# ESP_LoRa_1_0.net
KiCad netlist of a schematic drawn in EAGLE
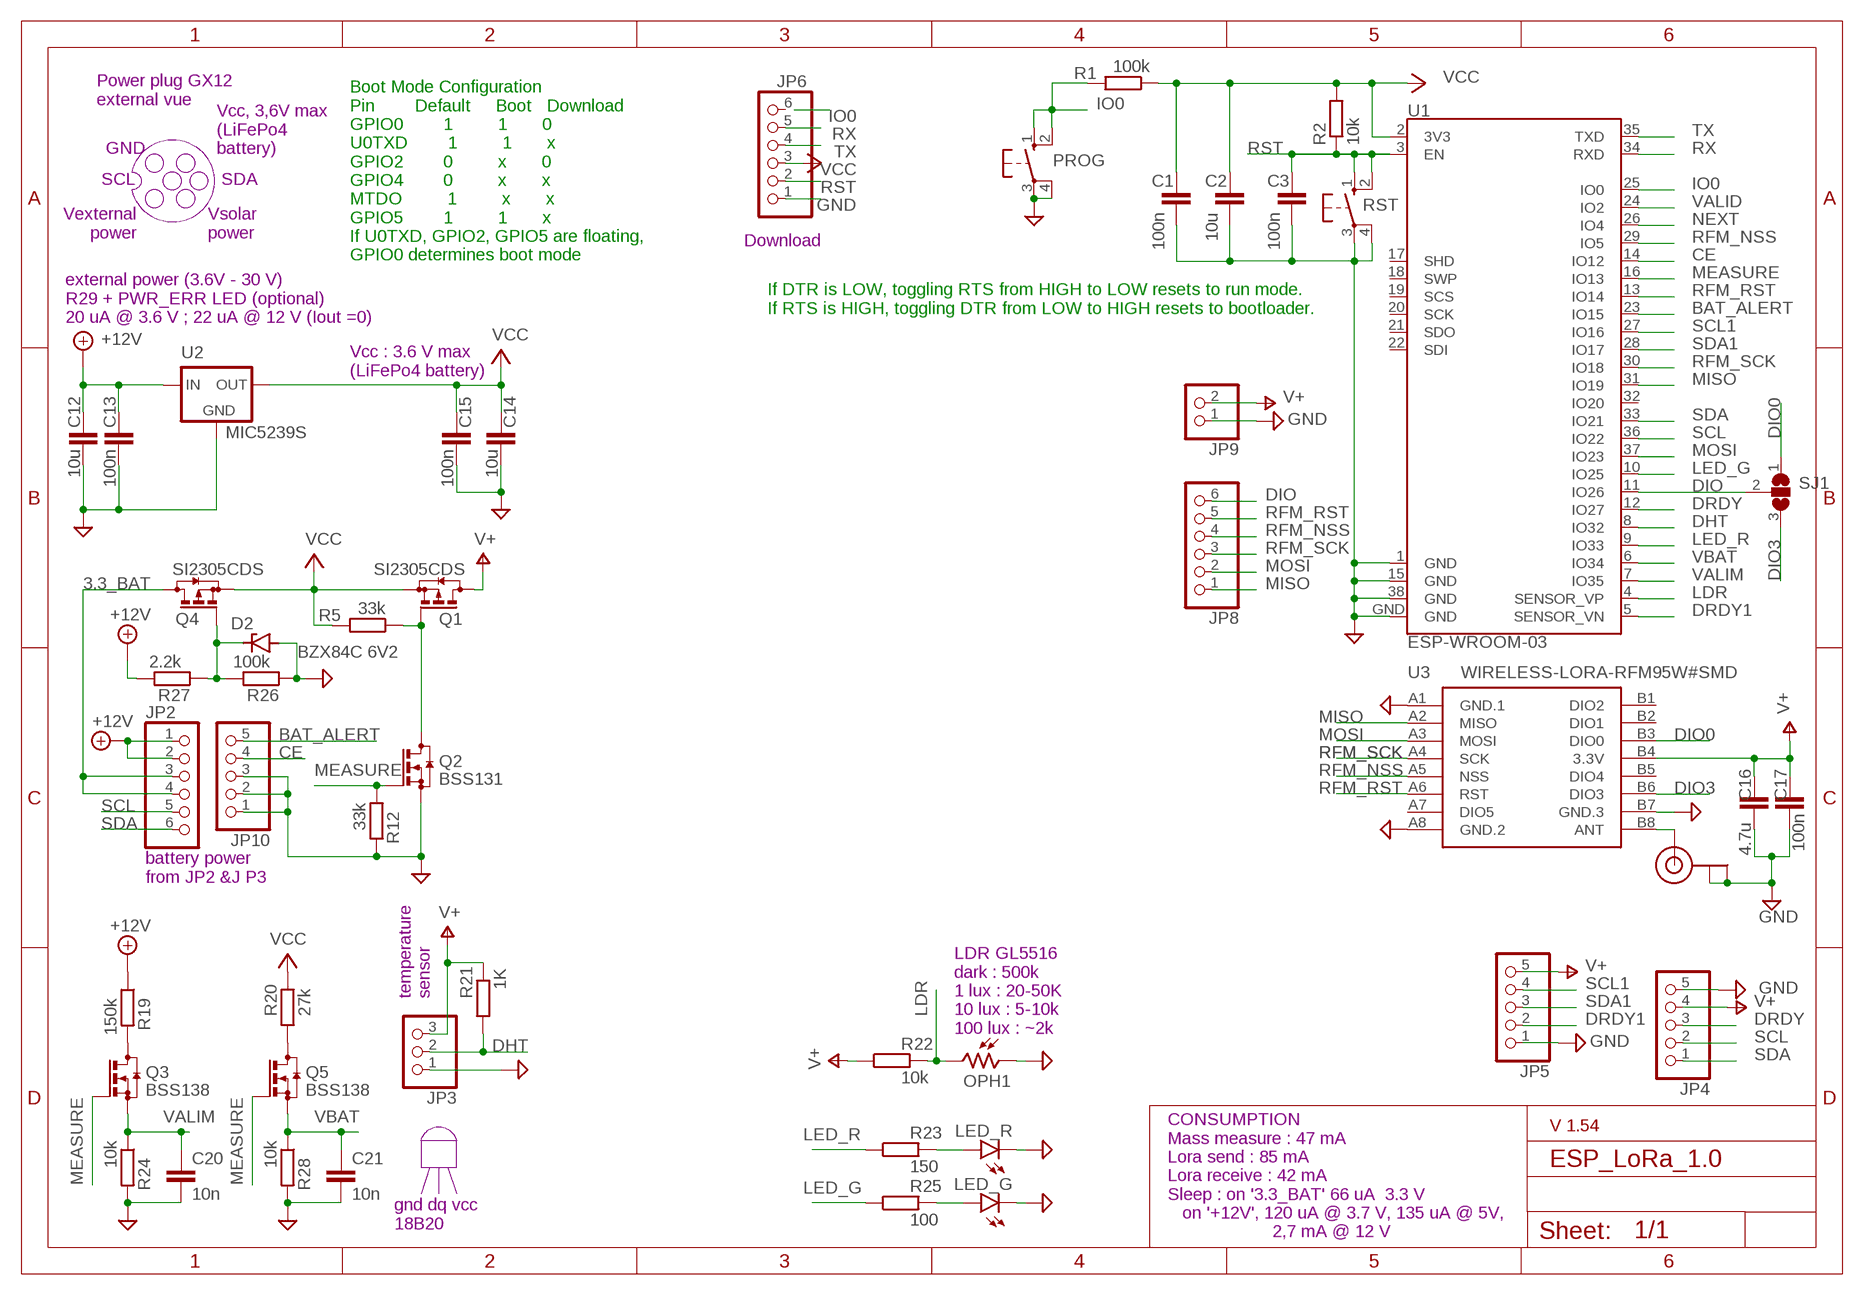
[diagram p0: schematic, sheet 1]

(export (version "E")
  (design (tool "Eeschema 10.0.6"))
  (components
    (comp (ref "C1")
      (value "100n")
      (footprint "eagle-import:C1206")
      (libsource (lib "eagle-import") (part "CC1206"))
    )
    (comp (ref "C2")
      (value "10u")
      (footprint "eagle-import:C1210")
      (libsource (lib "eagle-import") (part "CC1210"))
    )
    (comp (ref "C3")
      (value "100n")
      (footprint "eagle-import:C1206")
      (libsource (lib "eagle-import") (part "CC1206"))
    )
    (comp (ref "C12")
      (value "10u")
      (footprint "eagle-import:C1210")
      (libsource (lib "eagle-import") (part "CC1210"))
    )
    (comp (ref "C13")
      (value "100n")
      (footprint "eagle-import:C1206")
      (libsource (lib "eagle-import") (part "CC1206"))
    )
    (comp (ref "C14")
      (value "10u")
      (footprint "eagle-import:C1210")
      (libsource (lib "eagle-import") (part "CC1210"))
    )
    (comp (ref "C15")
      (value "100n")
      (footprint "eagle-import:C1206")
      (libsource (lib "eagle-import") (part "CC1206"))
    )
    (comp (ref "C16")
      (value "4.7u")
      (footprint "eagle-import:C1210")
      (libsource (lib "eagle-import") (part "CC1210"))
    )
    (comp (ref "C17")
      (value "100n")
      (footprint "eagle-import:C1206")
      (libsource (lib "eagle-import") (part "CC1206"))
    )
    (comp (ref "C20")
      (value "10n")
      (footprint "eagle-import:C1206")
      (libsource (lib "eagle-import") (part "CC1206"))
    )
    (comp (ref "C21")
      (value "10n")
      (footprint "eagle-import:C1206")
      (libsource (lib "eagle-import") (part "CC1206"))
    )
    (comp (ref "D2")
      (value "BZX84C 6V2")
      (footprint "eagle-import:TO236")
      (libsource (lib "eagle-import") (part "BZX84CSMD"))
    )
    (comp (ref "J1")
      (value "U.FL")
      (footprint "eagle-import:U.FL")
      (libsource (lib "eagle-import") (part "U.FL"))
    )
    (comp (ref "JP2")
      (value "PINHD-1X6")
      (footprint "eagle-import:1X06")
      (libsource (lib "eagle-import") (part "PINHD-1X6"))
    )
    (comp (ref "JP3")
      (value "PINHD-1X3")
      (footprint "eagle-import:1X03")
      (libsource (lib "eagle-import") (part "PINHD-1X3"))
    )
    (comp (ref "JP4")
      (value "PINHD-1X5")
      (footprint "eagle-import:1X05")
      (libsource (lib "eagle-import") (part "PINHD-1X5"))
    )
    (comp (ref "JP5")
      (value "PINHD-1X5")
      (footprint "eagle-import:1X05")
      (libsource (lib "eagle-import") (part "PINHD-1X5"))
    )
    (comp (ref "JP6")
      (value "PINHD-1X6")
      (footprint "eagle-import:1X06")
      (libsource (lib "eagle-import") (part "PINHD-1X6"))
    )
    (comp (ref "JP8")
      (value "PINHD-1X6")
      (footprint "eagle-import:1X06")
      (libsource (lib "eagle-import") (part "PINHD-1X6"))
    )
    (comp (ref "JP9")
      (value "PINHD-1X2")
      (footprint "eagle-import:1X02")
      (libsource (lib "eagle-import") (part "PINHD-1X2"))
    )
    (comp (ref "JP10")
      (value "PINHD-1X5")
      (footprint "eagle-import:1X05")
      (libsource (lib "eagle-import") (part "PINHD-1X5"))
    )
    (comp (ref "LED_G")
      (value "LEDSMT1206")
      (footprint "eagle-import:1206")
      (libsource (lib "eagle-import") (part "LEDSMT1206"))
    )
    (comp (ref "LED_R")
      (value "LEDSMT1206")
      (footprint "eagle-import:1206")
      (libsource (lib "eagle-import") (part "LEDSMT1206"))
    )
    (comp (ref "OPH1")
      (value "VT93N2")
      (footprint "eagle-import:VT900")
      (libsource (lib "eagle-import") (part "VT93N2"))
    )
    (comp (ref "PROG")
      (value "10-XX")
      (footprint "eagle-import:B3F-10XX")
      (fields (field (name "MPN") "B3F-1000"))
      (libsource (lib "eagle-import") (part "10-XX"))
    )
    (comp (ref "Q1")
      (value "SI2305CDS")
      (footprint "eagle-import:SOT23")
      (libsource (lib "eagle-import") (part "SI2305CDS"))
    )
    (comp (ref "Q2")
      (value "BSS131")
      (footprint "eagle-import:SOT23")
      (libsource (lib "eagle-import") (part "BSS131"))
    )
    (comp (ref "Q3")
      (value "BSS138")
      (footprint "eagle-import:SOT23")
      (libsource (lib "eagle-import") (part "BSS138"))
    )
    (comp (ref "Q4")
      (value "SI2305CDS")
      (footprint "eagle-import:SOT23")
      (libsource (lib "eagle-import") (part "SI2305CDS"))
    )
    (comp (ref "Q5")
      (value "BSS138")
      (footprint "eagle-import:SOT23")
      (libsource (lib "eagle-import") (part "BSS138"))
    )
    (comp (ref "R1")
      (value "100k")
      (footprint "eagle-import:R1206")
      (libsource (lib "eagle-import") (part "RR1206"))
    )
    (comp (ref "R2")
      (value "10k")
      (footprint "eagle-import:R1206")
      (libsource (lib "eagle-import") (part "RR1206"))
    )
    (comp (ref "R5")
      (value "33k")
      (footprint "eagle-import:R1206")
      (libsource (lib "eagle-import") (part "RR1206"))
    )
    (comp (ref "R12")
      (value "33k")
      (footprint "eagle-import:R1206")
      (libsource (lib "eagle-import") (part "RR1206"))
    )
    (comp (ref "R19")
      (value "150k")
      (footprint "eagle-import:R1206")
      (libsource (lib "eagle-import") (part "RR1206"))
    )
    (comp (ref "R20")
      (value "27k")
      (footprint "eagle-import:R1206")
      (libsource (lib "eagle-import") (part "RR1206"))
    )
    (comp (ref "R21")
      (value "1K")
      (footprint "eagle-import:R1206")
      (libsource (lib "eagle-import") (part "RR1206"))
    )
    (comp (ref "R22")
      (value "10k")
      (footprint "eagle-import:R1206")
      (libsource (lib "eagle-import") (part "RR1206"))
    )
    (comp (ref "R23")
      (value "150")
      (footprint "eagle-import:R1206")
      (libsource (lib "eagle-import") (part "RR1206"))
    )
    (comp (ref "R24")
      (value "10k")
      (footprint "eagle-import:R1206")
      (libsource (lib "eagle-import") (part "RR1206"))
    )
    (comp (ref "R25")
      (value "100")
      (footprint "eagle-import:R1206")
      (libsource (lib "eagle-import") (part "RR1206"))
    )
    (comp (ref "R26")
      (value "100k")
      (footprint "eagle-import:R1206")
      (libsource (lib "eagle-import") (part "RR1206"))
    )
    (comp (ref "R27")
      (value "2.2k")
      (footprint "eagle-import:R1206")
      (libsource (lib "eagle-import") (part "RR1206"))
    )
    (comp (ref "R28")
      (value "10k")
      (footprint "eagle-import:R1206")
      (libsource (lib "eagle-import") (part "RR1206"))
    )
    (comp (ref "RST")
      (value "10-XX")
      (footprint "eagle-import:B3F-10XX")
      (fields (field (name "MPN") "B3F-1000"))
      (libsource (lib "eagle-import") (part "10-XX"))
    )
    (comp (ref "SJ1")
      (value "SJ2W")
      (footprint "eagle-import:SJ_2")
      (libsource (lib "eagle-import") (part "SJ2W"))
    )
    (comp (ref "U1")
      (value "ESP-WROOM-03")
      (footprint "eagle-import:ESP-WROOM-03")
      (libsource (lib "eagle-import") (part "ESP-WROOM-03"))
    )
    (comp (ref "U2")
      (value "MIC5239S")
      (footprint "eagle-import:SOT223")
      (libsource (lib "eagle-import") (part "MIC5239S"))
    )
    (comp (ref "U3")
      (value "WIRELESS-LORA-RFM95W#SMD")
      (footprint "eagle-import:WIRELESS-LORA-RFM95W#SMD")
      (libsource (lib "eagle-import") (part "WIRELESS-LORA-RFM95W#SMD"))
    )
  )
  (nets
    (net (code "1") (name "+12V") (class "Default")
      (node (ref "C12") (pin "1") (pinfunction "1_1") (pintype "passive"))
      (node (ref "C13") (pin "1") (pinfunction "1_1") (pintype "passive"))
      (node (ref "JP2") (pin "1") (pinfunction "1_1") (pintype "passive"))
      (node (ref "JP2") (pin "2") (pinfunction "2_2") (pintype "passive"))
      (node (ref "R19") (pin "1") (pinfunction "1_1") (pintype "passive"))
      (node (ref "R27") (pin "2") (pinfunction "2_2") (pintype "passive"))
      (node (ref "U2") (pin "1") (pinfunction "IN_1") (pintype "input"))
    )
    (net (code "2") (name "/3.3_BAT") (class "Default")
      (node (ref "JP2") (pin "3") (pinfunction "3_3") (pintype "passive"))
      (node (ref "JP2") (pin "4") (pinfunction "4_4") (pintype "passive"))
      (node (ref "Q4") (pin "3") (pinfunction "D_3") (pintype "passive"))
    )
    (net (code "3") (name "/BAT_ALERT") (class "Default")
      (node (ref "JP10") (pin "5") (pinfunction "5_5") (pintype "passive"))
      (node (ref "U1") (pin "23") (pinfunction "IO15_23") (pintype "bidirectional"))
    )
    (net (code "4") (name "/CE") (class "Default")
      (node (ref "JP10") (pin "4") (pinfunction "4_4") (pintype "passive"))
      (node (ref "U1") (pin "14") (pinfunction "IO12_14") (pintype "bidirectional"))
    )
    (net (code "5") (name "/DHT") (class "Default")
      (node (ref "JP3") (pin "2") (pinfunction "2_2") (pintype "passive"))
      (node (ref "R21") (pin "1") (pinfunction "1_1") (pintype "passive"))
      (node (ref "U1") (pin "8") (pinfunction "IO32_8") (pintype "bidirectional"))
    )
    (net (code "6") (name "/DIO") (class "Default")
      (node (ref "JP8") (pin "6") (pinfunction "6_6") (pintype "passive"))
      (node (ref "SJ1") (pin "2") (pinfunction "2_2") (pintype "passive"))
      (node (ref "U1") (pin "11") (pinfunction "IO26_11") (pintype "bidirectional"))
    )
    (net (code "7") (name "/DIO0") (class "Default")
      (node (ref "SJ1") (pin "1") (pinfunction "1_1") (pintype "passive"))
      (node (ref "U3") (pin "B3") (pinfunction "DIO0_B3") (pintype "bidirectional"))
    )
    (net (code "8") (name "/DIO3") (class "Default")
      (node (ref "SJ1") (pin "3") (pinfunction "3_3") (pintype "passive"))
      (node (ref "U3") (pin "B6") (pinfunction "DIO3_B6") (pintype "bidirectional"))
    )
    (net (code "9") (name "/DRDY") (class "Default")
      (node (ref "JP4") (pin "3") (pinfunction "3_3") (pintype "passive"))
      (node (ref "U1") (pin "12") (pinfunction "IO27_12") (pintype "bidirectional"))
    )
    (net (code "10") (name "/DRDY1") (class "Default")
      (node (ref "JP5") (pin "2") (pinfunction "2_2") (pintype "passive"))
      (node (ref "U1") (pin "5") (pinfunction "SENSOR_VN_5") (pintype "bidirectional"))
    )
    (net (code "11") (name "/IO0") (class "Default")
      (node (ref "PROG") (pin "1") (pinfunction "S_1") (pintype "passive"))
      (node (ref "PROG") (pin "2") (pinfunction "S1_2") (pintype "passive"))
      (node (ref "R1") (pin "2") (pinfunction "2_2") (pintype "passive"))
      (node (ref "U1") (pin "25") (pinfunction "IO0_25") (pintype "bidirectional"))
    )
    (net (code "12") (name "/LDR") (class "Default")
      (node (ref "OPH1") (pin "2") (pinfunction "2_2") (pintype "passive"))
      (node (ref "R22") (pin "2") (pinfunction "2_2") (pintype "passive"))
      (node (ref "U1") (pin "4") (pinfunction "SENSOR_VP_4") (pintype "bidirectional"))
    )
    (net (code "13") (name "/LED_G") (class "Default")
      (node (ref "R25") (pin "1") (pinfunction "1_1") (pintype "passive"))
      (node (ref "U1") (pin "10") (pinfunction "IO25_10") (pintype "bidirectional"))
    )
    (net (code "14") (name "/LED_R") (class "Default")
      (node (ref "R23") (pin "1") (pinfunction "1_1") (pintype "passive"))
      (node (ref "U1") (pin "9") (pinfunction "IO33_9") (pintype "bidirectional"))
    )
    (net (code "15") (name "/MEASURE") (class "Default")
      (node (ref "Q2") (pin "1") (pinfunction "G_1") (pintype "passive"))
      (node (ref "Q3") (pin "1") (pinfunction "G_1") (pintype "passive"))
      (node (ref "Q5") (pin "1") (pinfunction "G_1") (pintype "passive"))
      (node (ref "R12") (pin "1") (pinfunction "1_1") (pintype "passive"))
      (node (ref "U1") (pin "16") (pinfunction "IO13_16") (pintype "bidirectional"))
    )
    (net (code "16") (name "/MISO") (class "Default")
      (node (ref "JP8") (pin "1") (pinfunction "1_1") (pintype "passive"))
      (node (ref "U1") (pin "31") (pinfunction "IO19_31") (pintype "bidirectional"))
      (node (ref "U3") (pin "A2") (pinfunction "MISO_A2") (pintype "bidirectional"))
    )
    (net (code "17") (name "/MOSI") (class "Default")
      (node (ref "JP8") (pin "2") (pinfunction "2_2") (pintype "passive"))
      (node (ref "U1") (pin "37") (pinfunction "IO23_37") (pintype "bidirectional"))
      (node (ref "U3") (pin "A3") (pinfunction "MOSI_A3") (pintype "bidirectional"))
    )
    (net (code "18") (name "/NEXT") (class "Default")
      (node (ref "U1") (pin "26") (pinfunction "IO4_26") (pintype "bidirectional"))
    )
    (net (code "19") (name "/RFM_NSS") (class "Default")
      (node (ref "JP8") (pin "4") (pinfunction "4_4") (pintype "passive"))
      (node (ref "U1") (pin "29") (pinfunction "IO5_29") (pintype "bidirectional"))
      (node (ref "U3") (pin "A5") (pinfunction "NSS_A5") (pintype "bidirectional"))
    )
    (net (code "20") (name "/RFM_RST") (class "Default")
      (node (ref "JP8") (pin "5") (pinfunction "5_5") (pintype "passive"))
      (node (ref "U1") (pin "13") (pinfunction "IO14_13") (pintype "bidirectional"))
      (node (ref "U3") (pin "A6") (pinfunction "RST_A6") (pintype "bidirectional"))
    )
    (net (code "21") (name "/RFM_SCK") (class "Default")
      (node (ref "JP8") (pin "3") (pinfunction "3_3") (pintype "passive"))
      (node (ref "U1") (pin "30") (pinfunction "IO18_30") (pintype "bidirectional"))
      (node (ref "U3") (pin "A4") (pinfunction "SCK_A4") (pintype "bidirectional"))
    )
    (net (code "22") (name "/RST") (class "Default")
      (node (ref "C3") (pin "1") (pinfunction "1_1") (pintype "passive"))
      (node (ref "JP6") (pin "2") (pinfunction "2_2") (pintype "passive"))
      (node (ref "R2") (pin "1") (pinfunction "1_1") (pintype "passive"))
      (node (ref "RST") (pin "1") (pinfunction "S_1") (pintype "passive"))
      (node (ref "RST") (pin "2") (pinfunction "S1_2") (pintype "passive"))
      (node (ref "U1") (pin "3") (pinfunction "EN_3") (pintype "bidirectional"))
    )
    (net (code "23") (name "/RX") (class "Default")
      (node (ref "JP6") (pin "5") (pinfunction "5_5") (pintype "passive"))
      (node (ref "U1") (pin "34") (pinfunction "RXD_34") (pintype "bidirectional"))
    )
    (net (code "24") (name "/SCL") (class "Default")
      (node (ref "JP2") (pin "5") (pinfunction "5_5") (pintype "passive"))
      (node (ref "JP4") (pin "2") (pinfunction "2_2") (pintype "passive"))
      (node (ref "U1") (pin "36") (pinfunction "IO22_36") (pintype "bidirectional"))
    )
    (net (code "25") (name "/SCL1") (class "Default")
      (node (ref "JP5") (pin "4") (pinfunction "4_4") (pintype "passive"))
      (node (ref "U1") (pin "27") (pinfunction "IO16_27") (pintype "bidirectional"))
    )
    (net (code "26") (name "/SDA") (class "Default")
      (node (ref "JP2") (pin "6") (pinfunction "6_6") (pintype "passive"))
      (node (ref "JP4") (pin "1") (pinfunction "1_1") (pintype "passive"))
      (node (ref "U1") (pin "33") (pinfunction "IO21_33") (pintype "bidirectional"))
    )
    (net (code "27") (name "/SDA1") (class "Default")
      (node (ref "JP5") (pin "3") (pinfunction "3_3") (pintype "passive"))
      (node (ref "U1") (pin "28") (pinfunction "IO17_28") (pintype "bidirectional"))
    )
    (net (code "28") (name "/TX") (class "Default")
      (node (ref "JP6") (pin "4") (pinfunction "4_4") (pintype "passive"))
      (node (ref "U1") (pin "35") (pinfunction "TXD_35") (pintype "bidirectional"))
    )
    (net (code "29") (name "/VALID") (class "Default")
      (node (ref "U1") (pin "24") (pinfunction "IO2_24") (pintype "bidirectional"))
    )
    (net (code "30") (name "/VALIM") (class "Default")
      (node (ref "C20") (pin "1") (pinfunction "1_1") (pintype "passive"))
      (node (ref "Q3") (pin "2") (pinfunction "S_2") (pintype "passive"))
      (node (ref "R24") (pin "1") (pinfunction "1_1") (pintype "passive"))
      (node (ref "U1") (pin "7") (pinfunction "IO35_7") (pintype "bidirectional"))
    )
    (net (code "31") (name "/VBAT") (class "Default")
      (node (ref "C21") (pin "1") (pinfunction "1_1") (pintype "passive"))
      (node (ref "Q5") (pin "2") (pinfunction "S_2") (pintype "passive"))
      (node (ref "R28") (pin "1") (pinfunction "1_1") (pintype "passive"))
      (node (ref "U1") (pin "6") (pinfunction "IO34_6") (pintype "bidirectional"))
    )
    (net (code "32") (name "GND") (class "Default")
      (node (ref "C1") (pin "2") (pinfunction "2_2") (pintype "passive"))
      (node (ref "C12") (pin "2") (pinfunction "2_2") (pintype "passive"))
      (node (ref "C13") (pin "2") (pinfunction "2_2") (pintype "passive"))
      (node (ref "C14") (pin "2") (pinfunction "2_2") (pintype "passive"))
      (node (ref "C15") (pin "2") (pinfunction "2_2") (pintype "passive"))
      (node (ref "C16") (pin "2") (pinfunction "2_2") (pintype "passive"))
      (node (ref "C17") (pin "2") (pinfunction "2_2") (pintype "passive"))
      (node (ref "C2") (pin "2") (pinfunction "2_2") (pintype "passive"))
      (node (ref "C20") (pin "2") (pinfunction "2_2") (pintype "passive"))
      (node (ref "C21") (pin "2") (pinfunction "2_2") (pintype "passive"))
      (node (ref "C3") (pin "2") (pinfunction "2_2") (pintype "passive"))
      (node (ref "D2") (pin "A") (pinfunction "A_A") (pintype "passive"))
      (node (ref "J1") (pin "1") (pinfunction "GND_1") (pintype "passive"))
      (node (ref "J1") (pin "2") (pinfunction "GND_2") (pintype "passive"))
      (node (ref "JP10") (pin "1") (pinfunction "1_1") (pintype "passive"))
      (node (ref "JP10") (pin "2") (pinfunction "2_2") (pintype "passive"))
      (node (ref "JP10") (pin "3") (pinfunction "3_3") (pintype "passive"))
      (node (ref "JP3") (pin "1") (pinfunction "1_1") (pintype "passive"))
      (node (ref "JP4") (pin "5") (pinfunction "5_5") (pintype "passive"))
      (node (ref "JP5") (pin "1") (pinfunction "1_1") (pintype "passive"))
      (node (ref "JP6") (pin "1") (pinfunction "1_1") (pintype "passive"))
      (node (ref "JP9") (pin "1") (pinfunction "1_1") (pintype "passive"))
      (node (ref "LED_G") (pin "C") (pinfunction "C_C") (pintype "passive"))
      (node (ref "LED_R") (pin "C") (pinfunction "C_C") (pintype "passive"))
      (node (ref "OPH1") (pin "1") (pinfunction "1_1") (pintype "passive"))
      (node (ref "PROG") (pin "3") (pinfunction "P_3") (pintype "passive"))
      (node (ref "PROG") (pin "4") (pinfunction "P1_4") (pintype "passive"))
      (node (ref "Q2") (pin "2") (pinfunction "S_2") (pintype "passive"))
      (node (ref "R12") (pin "2") (pinfunction "2_2") (pintype "passive"))
      (node (ref "R24") (pin "2") (pinfunction "2_2") (pintype "passive"))
      (node (ref "R26") (pin "1") (pinfunction "1_1") (pintype "passive"))
      (node (ref "R28") (pin "2") (pinfunction "2_2") (pintype "passive"))
      (node (ref "RST") (pin "3") (pinfunction "P_3") (pintype "passive"))
      (node (ref "RST") (pin "4") (pinfunction "P1_4") (pintype "passive"))
      (node (ref "U1") (pin "1") (pinfunction "GND_1") (pintype "bidirectional"))
      (node (ref "U1") (pin "15") (pinfunction "GND_15") (pintype "bidirectional"))
      (node (ref "U1") (pin "38") (pinfunction "GND_38") (pintype "bidirectional"))
      (node (ref "U1") (pin "GND") (pinfunction "GND_GND") (pintype "bidirectional"))
      (node (ref "U2") (pin "2") (pinfunction "GND_2") (pintype "passive"))
      (node (ref "U2") (pin "4") (pinfunction "GND_4") (pintype "passive"))
      (node (ref "U3") (pin "A1") (pinfunction "GND.1_A1") (pintype "power_in"))
      (node (ref "U3") (pin "A8") (pinfunction "GND.2_A8") (pintype "power_in"))
      (node (ref "U3") (pin "B7") (pinfunction "GND.3_B7") (pintype "power_in"))
    )
    (net (code "33") (name "Net-(J1-SIGNAL)") (class "Default")
      (node (ref "J1") (pin "3") (pinfunction "SIGNAL_3") (pintype "passive"))
      (node (ref "U3") (pin "B8") (pinfunction "ANT_B8") (pintype "passive"))
    )
    (net (code "34") (name "Net-(LED_G-PadA)") (class "Default")
      (node (ref "LED_G") (pin "A") (pinfunction "A_A") (pintype "passive"))
      (node (ref "R25") (pin "2") (pinfunction "2_2") (pintype "passive"))
    )
    (net (code "35") (name "Net-(LED_R-PadA)") (class "Default")
      (node (ref "LED_R") (pin "A") (pinfunction "A_A") (pintype "passive"))
      (node (ref "R23") (pin "2") (pinfunction "2_2") (pintype "passive"))
    )
    (net (code "36") (name "Net-(Q1-G)") (class "Default")
      (node (ref "Q1") (pin "1") (pinfunction "G_1") (pintype "passive"))
      (node (ref "Q2") (pin "3") (pinfunction "D_3") (pintype "passive"))
      (node (ref "R5") (pin "1") (pinfunction "1_1") (pintype "passive"))
    )
    (net (code "37") (name "Net-(Q3-D)") (class "Default")
      (node (ref "Q3") (pin "3") (pinfunction "D_3") (pintype "passive"))
      (node (ref "R19") (pin "2") (pinfunction "2_2") (pintype "passive"))
    )
    (net (code "38") (name "Net-(Q4-G)") (class "Default")
      (node (ref "D2") (pin "C") (pinfunction "C_C") (pintype "passive"))
      (node (ref "Q4") (pin "1") (pinfunction "G_1") (pintype "passive"))
      (node (ref "R26") (pin "2") (pinfunction "2_2") (pintype "passive"))
      (node (ref "R27") (pin "1") (pinfunction "1_1") (pintype "passive"))
    )
    (net (code "39") (name "Net-(Q5-D)") (class "Default")
      (node (ref "Q5") (pin "3") (pinfunction "D_3") (pintype "passive"))
      (node (ref "R20") (pin "1") (pinfunction "1_1") (pintype "passive"))
    )
    (net (code "40") (name "V+") (class "Default")
      (node (ref "C16") (pin "1") (pinfunction "1_1") (pintype "passive"))
      (node (ref "C17") (pin "1") (pinfunction "1_1") (pintype "passive"))
      (node (ref "JP3") (pin "3") (pinfunction "3_3") (pintype "passive"))
      (node (ref "JP4") (pin "4") (pinfunction "4_4") (pintype "passive"))
      (node (ref "JP5") (pin "5") (pinfunction "5_5") (pintype "passive"))
      (node (ref "JP9") (pin "2") (pinfunction "2_2") (pintype "passive"))
      (node (ref "Q1") (pin "3") (pinfunction "D_3") (pintype "passive"))
      (node (ref "R21") (pin "2") (pinfunction "2_2") (pintype "passive"))
      (node (ref "R22") (pin "1") (pinfunction "1_1") (pintype "passive"))
      (node (ref "U3") (pin "B4") (pinfunction "3.3V_B4") (pintype "power_in"))
    )
    (net (code "41") (name "VCC") (class "Default")
      (node (ref "C1") (pin "1") (pinfunction "1_1") (pintype "passive"))
      (node (ref "C14") (pin "1") (pinfunction "1_1") (pintype "passive"))
      (node (ref "C15") (pin "1") (pinfunction "1_1") (pintype "passive"))
      (node (ref "C2") (pin "1") (pinfunction "1_1") (pintype "passive"))
      (node (ref "JP6") (pin "3") (pinfunction "3_3") (pintype "passive"))
      (node (ref "Q1") (pin "2") (pinfunction "S_2") (pintype "passive"))
      (node (ref "Q4") (pin "2") (pinfunction "S_2") (pintype "passive"))
      (node (ref "R1") (pin "1") (pinfunction "1_1") (pintype "passive"))
      (node (ref "R2") (pin "2") (pinfunction "2_2") (pintype "passive"))
      (node (ref "R20") (pin "2") (pinfunction "2_2") (pintype "passive"))
      (node (ref "R5") (pin "2") (pinfunction "2_2") (pintype "passive"))
      (node (ref "U1") (pin "2") (pinfunction "3V3_2") (pintype "bidirectional"))
      (node (ref "U2") (pin "3") (pinfunction "OUT_3") (pintype "passive"))
    )
    (net (code "42") (name "unconnected-(JP6-Pad6)") (class "Default")
      (node (ref "JP6") (pin "6") (pinfunction "6_6") (pintype "passive"))
    )
    (net (code "43") (name "unconnected-(U1-IO20-Pad32)") (class "Default")
      (node (ref "U1") (pin "32") (pinfunction "IO20_32") (pintype "bidirectional"))
    )
    (net (code "44") (name "unconnected-(U1-SCK-Pad20)") (class "Default")
      (node (ref "U1") (pin "20") (pinfunction "SCK_20") (pintype "bidirectional"))
    )
    (net (code "45") (name "unconnected-(U1-SCS-Pad19)") (class "Default")
      (node (ref "U1") (pin "19") (pinfunction "SCS_19") (pintype "bidirectional"))
    )
    (net (code "46") (name "unconnected-(U1-SDI-Pad22)") (class "Default")
      (node (ref "U1") (pin "22") (pinfunction "SDI_22") (pintype "bidirectional"))
    )
    (net (code "47") (name "unconnected-(U1-SDO-Pad21)") (class "Default")
      (node (ref "U1") (pin "21") (pinfunction "SDO_21") (pintype "bidirectional"))
    )
    (net (code "48") (name "unconnected-(U1-SHD-Pad17)") (class "Default")
      (node (ref "U1") (pin "17") (pinfunction "SHD_17") (pintype "bidirectional"))
    )
    (net (code "49") (name "unconnected-(U1-SWP-Pad18)") (class "Default")
      (node (ref "U1") (pin "18") (pinfunction "SWP_18") (pintype "bidirectional"))
    )
    (net (code "50") (name "unconnected-(U3-DIO1-PadB2)") (class "Default")
      (node (ref "U3") (pin "B2") (pinfunction "DIO1_B2") (pintype "bidirectional"))
    )
    (net (code "51") (name "unconnected-(U3-DIO2-PadB1)") (class "Default")
      (node (ref "U3") (pin "B1") (pinfunction "DIO2_B1") (pintype "bidirectional"))
    )
    (net (code "52") (name "unconnected-(U3-DIO4-PadB5)") (class "Default")
      (node (ref "U3") (pin "B5") (pinfunction "DIO4_B5") (pintype "bidirectional"))
    )
    (net (code "53") (name "unconnected-(U3-DIO5-PadA7)") (class "Default")
      (node (ref "U3") (pin "A7") (pinfunction "DIO5_A7") (pintype "bidirectional"))
    )
  )
)
